# PULSE_COUNTER.net
KiCad netlist of a schematic drawn in Altium Designer
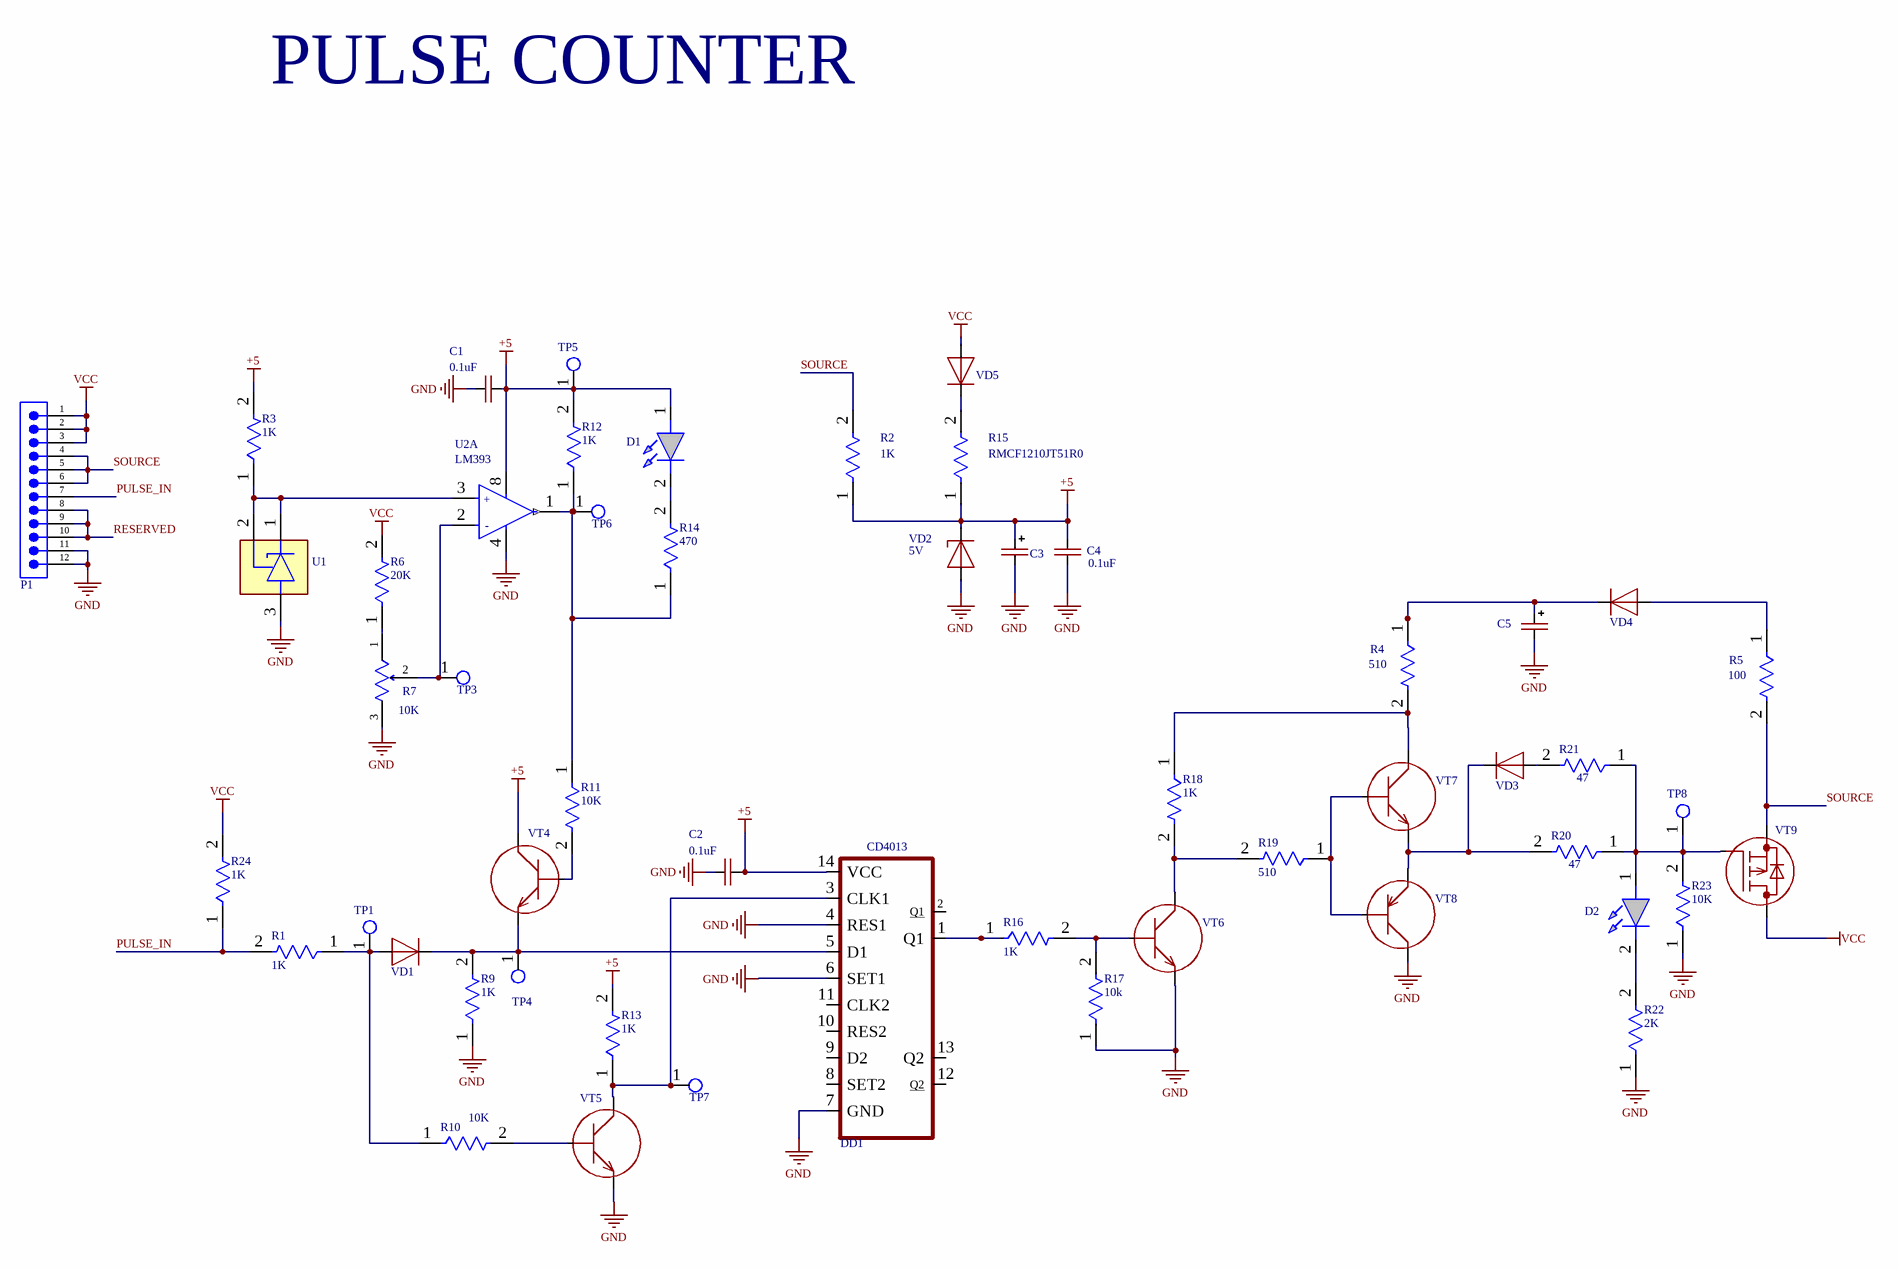
[diagram p0: PULSE COUNTER.SchDoc]

(export (version "E")
  (design (tool "Eeschema 10.0.6"))
  (components
    (comp (ref "C1")
      (value "0.1uF")
      (footprint "CAP-0805")
      (libsource (lib "PASSIVE_COMPONENTS") (part "CAP-NON-POLAR"))
    )
    (comp (ref "C2")
      (value "0.1uF")
      (footprint "CAP-0805")
      (libsource (lib "PASSIVE_COMPONENTS") (part "CAP-NON-POLAR"))
    )
    (comp (ref "C3")
      (value "CAP-POLAR")
      (footprint "CAP-TAN-D")
      (libsource (lib "PASSIVE_COMPONENTS") (part "CAP-POLAR"))
    )
    (comp (ref "C4")
      (value "0.1uF")
      (footprint "CAP-0805")
      (libsource (lib "PASSIVE_COMPONENTS") (part "CAP-NON-POLAR"))
    )
    (comp (ref "C5")
      (value "CAP-POLAR")
      (footprint "SIZE_EEE")
      (libsource (lib "PASSIVE_COMPONENTS") (part "CAP-POLAR"))
    )
    (comp (ref "D1")
      (value "151031YS06000")
      (footprint "LED_RED")
      (description "WURTH ELEKTRONIK - 151031YS06000 - LED, Yellow, Through Hole, T-1 (3mm), 30 mA, 2 V, 590 nm")
      (fields (field (name "MOUSER PART NUMBER") "710-151031YS06000"))
      (libsource (lib "Optic-LED") (part "LED"))
    )
    (comp (ref "D2")
      (value "151031YS06000")
      (footprint "LED_RED")
      (description "WURTH ELEKTRONIK - 151031YS06000 - LED, Yellow, Through Hole, T-1 (3mm), 30 mA, 2 V, 590 nm")
      (fields (field (name "MOUSER PART NUMBER") "710-151031YS06000"))
      (libsource (lib "Optic-LED") (part "LED"))
    )
    (comp (ref "DD1") (value "CD4013") (footprint "SO14-150") (libsource (lib "CD4013") (part "CD4013")))
    (comp (ref "P1")
      (value "61301211021")
      (footprint "61301211021")
      (description "WR-PHD Pin Header, THT, Angled, pitch 2.54mm, 1 Row, 12P")
      (fields (field (name "MANUFACTURER") "Wurth Elektronik"))
      (libsource (lib "Altium_WR-PHD (rev22b)") (part "61301211021"))
    )
    (comp (ref "R1")
      (value "1K")
      (footprint "RES-0805")
      (libsource (lib "PASSIVE_COMPONENTS") (part "RES-CONST"))
    )
    (comp (ref "R2")
      (value "1K")
      (footprint "FP-RMCF1210-MFG")
      (fields (field (name "TOLERANCE") "5%"))
      (libsource (lib "Altium Content Vault") (part "1029c3af85768c4190bb7ad29bc67b5"))
    )
    (comp (ref "R3")
      (value "1K")
      (footprint "RES-0805")
      (libsource (lib "PASSIVE_COMPONENTS") (part "RES-CONST"))
    )
    (comp (ref "R4")
      (value "510")
      (footprint "RES-0805")
      (libsource (lib "PASSIVE_COMPONENTS") (part "RES-CONST"))
    )
    (comp (ref "R5")
      (value "100")
      (footprint "RES-0805")
      (description "510")
      (libsource (lib "PASSIVE_COMPONENTS") (part "RES-CONST"))
    )
    (comp (ref "R6")
      (value "20K")
      (footprint "RES-0805")
      (libsource (lib "PASSIVE_COMPONENTS") (part "RES-CONST"))
    )
    (comp (ref "R7")
      (value "10K")
      (footprint "RES_Adj_3296W_Bourns")
      (libsource (lib "PASSIVE_COMPONENTS") (part "RES_Adj"))
    )
    (comp (ref "R9")
      (value "1K")
      (footprint "RES-0805")
      (libsource (lib "PASSIVE_COMPONENTS") (part "RES-CONST"))
    )
    (comp (ref "R10")
      (value "10K")
      (footprint "RES-0805")
      (libsource (lib "PASSIVE_COMPONENTS") (part "RES-CONST"))
    )
    (comp (ref "R11")
      (value "10K")
      (footprint "RES-0805")
      (libsource (lib "PASSIVE_COMPONENTS") (part "RES-CONST"))
    )
    (comp (ref "R12")
      (value "1K")
      (footprint "RES-0805")
      (libsource (lib "PASSIVE_COMPONENTS") (part "RES-CONST"))
    )
    (comp (ref "R13")
      (value "1K")
      (footprint "RES-0805")
      (libsource (lib "PASSIVE_COMPONENTS") (part "RES-CONST"))
    )
    (comp (ref "R14")
      (value "470")
      (footprint "RES-0805")
      (description "1K")
      (libsource (lib "PASSIVE_COMPONENTS") (part "RES-CONST"))
    )
    (comp (ref "R15")
      (value "RMCF1210JT51R0")
      (footprint "FP-RMCF1210-MFG")
      (description "51Ω ±5% 0.5W 1210 Thick Film Chip Resistor AEC-Q200 compliant")
      (fields (field (name "TOLERANCE") "5%"))
      (libsource (lib "Altium Content Vault") (part "1029c3af85768c4190bb7ad29bc67b5"))
    )
    (comp (ref "R16")
      (value "1K")
      (footprint "RES-0805")
      (description "10K")
      (libsource (lib "PASSIVE_COMPONENTS") (part "RES-CONST"))
    )
    (comp (ref "R17")
      (value "10k")
      (footprint "RES-0805")
      (description "10K")
      (libsource (lib "PASSIVE_COMPONENTS") (part "RES-CONST"))
    )
    (comp (ref "R18")
      (value "1K")
      (footprint "RES-0805")
      (description "10K")
      (libsource (lib "PASSIVE_COMPONENTS") (part "RES-CONST"))
    )
    (comp (ref "R19")
      (value "510")
      (footprint "RES-0805")
      (libsource (lib "PASSIVE_COMPONENTS") (part "RES-CONST"))
    )
    (comp (ref "R20")
      (value "47")
      (footprint "RES-0805")
      (description "10K")
      (libsource (lib "PASSIVE_COMPONENTS") (part "RES-CONST"))
    )
    (comp (ref "R21")
      (value "47")
      (footprint "RES-0805")
      (description "10K")
      (libsource (lib "PASSIVE_COMPONENTS") (part "RES-CONST"))
    )
    (comp (ref "R22")
      (value "2K")
      (footprint "RES-0805")
      (libsource (lib "PASSIVE_COMPONENTS") (part "RES-CONST"))
    )
    (comp (ref "R23")
      (value "10K")
      (footprint "RES-0805")
      (libsource (lib "PASSIVE_COMPONENTS") (part "RES-CONST"))
    )
    (comp (ref "R24")
      (value "1K")
      (footprint "RES-0805")
      (libsource (lib "PASSIVE_COMPONENTS") (part "RES-CONST"))
    )
    (comp (ref "TP1")
      (value "~")
      (footprint "Test_Point")
      (description "Test_Point")
      (libsource (lib "Connectors") (part "TP_PCB?"))
    )
    (comp (ref "TP3")
      (value "~")
      (footprint "Test_Point")
      (description "Test_Point")
      (libsource (lib "Connectors") (part "TP_PCB?"))
    )
    (comp (ref "TP4")
      (value "~")
      (footprint "Test_Point")
      (description "Test_Point")
      (libsource (lib "Connectors") (part "TP_PCB?"))
    )
    (comp (ref "TP5")
      (value "~")
      (footprint "Test_Point")
      (description "Test_Point")
      (libsource (lib "Connectors") (part "TP_PCB?"))
    )
    (comp (ref "TP6")
      (value "~")
      (footprint "Test_Point")
      (description "Test_Point")
      (libsource (lib "Connectors") (part "TP_PCB?"))
    )
    (comp (ref "TP7")
      (value "~")
      (footprint "Test_Point")
      (description "Test_Point")
      (libsource (lib "Connectors") (part "TP_PCB?"))
    )
    (comp (ref "TP8")
      (value "~")
      (footprint "Test_Point")
      (description "Test_Point")
      (libsource (lib "Connectors") (part "TP_PCB?"))
    )
    (comp (ref "U1")
      (value "TL431")
      (footprint "TL431_SOT-23-3(A)")
      (description "TL431_SOT-23-3")
      (libsource (lib "Diodes") (part "TL431_SOT-23-3"))
    )
    (comp (ref "U2")
      (value "LM393")
      (footprint "FP-751-07-IPC_C")
      (description "IC OPAMP GP 2 CIRCUIT 8SOIC")
      (libsource (lib "Altium Content Vault") (part "992a6607d1d88c80ee6b45e5ba6cb1b"))
    )
    (comp (ref "VD1") (value "DIODE") (footprint "DO-214AC, SMA") (libsource (lib "DO214") (part "DIODE")))
    (comp (ref "VD2") (value "5V") (footprint "DO-017AA") (libsource (lib "Diodes") (part "ZENER")))
    (comp (ref "VD3") (value "DIODE") (footprint "DO-214AC, SMA") (libsource (lib "DO214") (part "DIODE")))
    (comp (ref "VD4") (value "DIODE") (footprint "DO-214AC, SMA") (libsource (lib "DO214") (part "DIODE")))
    (comp (ref "VD5") (value "DIODE") (footprint "DO-214AC, SMA") (libsource (lib "DO214") (part "DIODE")))
    (comp (ref "VT4") (value "BC847-BEC") (footprint "SOT23-3") (libsource (lib "BC8XX") (part "BC847-BEC")))
    (comp (ref "VT5") (value "BC847-BEC") (footprint "SOT23-3") (libsource (lib "BC8XX") (part "BC847-BEC")))
    (comp (ref "VT6") (value "BC847-BEC") (footprint "SOT23-3") (libsource (lib "BC8XX") (part "BC847-BEC")))
    (comp (ref "VT7") (value "BC847-BEC") (footprint "SOT23-3") (libsource (lib "BC8XX") (part "BC847-BEC")))
    (comp (ref "VT8") (value "BC857-BEC") (footprint "SOT23-3") (libsource (lib "BC8XX") (part "BC857-BEC")))
    (comp (ref "VT9")
      (value "MOSFET-P-CH-DPAK")
      (footprint "DPAK")
      (libsource (lib "IRFR9120N") (part "MOSFET-P-CH-DPAK"))
    )
  )
  (nets
    (net (code "1") (name "+5") (class "Default")
      (node (ref "C1") (pin "2") (pinfunction "2_2") (pintype "passive"))
      (node (ref "C2") (pin "2") (pinfunction "2_2") (pintype "passive"))
      (node (ref "C3") (pin "1") (pinfunction "+_1") (pintype "passive"))
      (node (ref "C4") (pin "2") (pinfunction "2_2") (pintype "passive"))
      (node (ref "D1") (pin "1") (pinfunction "A_1") (pintype "passive"))
      (node (ref "DD1") (pin "14") (pinfunction "VCC_14") (pintype "passive"))
      (node (ref "R12") (pin "2") (pinfunction "2_2") (pintype "passive"))
      (node (ref "R13") (pin "2") (pinfunction "2_2") (pintype "passive"))
      (node (ref "R15") (pin "1") (pinfunction "1_1") (pintype "passive"))
      (node (ref "R2") (pin "1") (pinfunction "1_1") (pintype "passive"))
      (node (ref "R3") (pin "2") (pinfunction "2_2") (pintype "passive"))
      (node (ref "TP5") (pin "1") (pinfunction "G9_1") (pintype "passive"))
      (node (ref "U2") (pin "8") (pinfunction "VCC_8") (pintype "power_in"))
      (node (ref "VD2") (pin "1") (pinfunction "C_1") (pintype "passive"))
      (node (ref "VT4") (pin "3") (pinfunction "C_3") (pintype "passive"))
    )
    (net (code "2") (name "/PULSE_IN") (class "Default")
      (node (ref "P1") (pin "7") (pinfunction "7_7") (pintype "passive"))
      (node (ref "R1") (pin "2") (pinfunction "2_2") (pintype "passive"))
      (node (ref "R24") (pin "1") (pinfunction "1_1") (pintype "passive"))
    )
    (net (code "3") (name "/RESERVED") (class "Default")
      (node (ref "P1") (pin "10") (pinfunction "10_10") (pintype "passive"))
      (node (ref "P1") (pin "8") (pinfunction "8_8") (pintype "passive"))
      (node (ref "P1") (pin "9") (pinfunction "9_9") (pintype "passive"))
    )
    (net (code "4") (name "/SOURCE") (class "Default")
      (node (ref "P1") (pin "4") (pinfunction "4_4") (pintype "passive"))
      (node (ref "P1") (pin "5") (pinfunction "5_5") (pintype "passive"))
      (node (ref "P1") (pin "6") (pinfunction "6_6") (pintype "passive"))
      (node (ref "R2") (pin "2") (pinfunction "2_2") (pintype "passive"))
      (node (ref "R5") (pin "2") (pinfunction "2_2") (pintype "passive"))
      (node (ref "VT9") (pin "3") (pinfunction "S_3") (pintype "passive"))
    )
    (net (code "5") (name "GND") (class "Default")
      (node (ref "C1") (pin "1") (pinfunction "1_1") (pintype "passive"))
      (node (ref "C2") (pin "1") (pinfunction "1_1") (pintype "passive"))
      (node (ref "C3") (pin "2") (pinfunction "-_2") (pintype "passive"))
      (node (ref "C4") (pin "1") (pinfunction "1_1") (pintype "passive"))
      (node (ref "C5") (pin "2") (pinfunction "-_2") (pintype "passive"))
      (node (ref "DD1") (pin "4") (pinfunction "RES1_4") (pintype "passive"))
      (node (ref "DD1") (pin "6") (pinfunction "SET1_6") (pintype "passive"))
      (node (ref "DD1") (pin "7") (pinfunction "GND_7") (pintype "passive"))
      (node (ref "P1") (pin "11") (pinfunction "11_11") (pintype "passive"))
      (node (ref "P1") (pin "12") (pinfunction "12_12") (pintype "passive"))
      (node (ref "R17") (pin "1") (pinfunction "1_1") (pintype "passive"))
      (node (ref "R22") (pin "1") (pinfunction "1_1") (pintype "passive"))
      (node (ref "R23") (pin "1") (pinfunction "1_1") (pintype "passive"))
      (node (ref "R7") (pin "3") (pinfunction "CW_3") (pintype "passive"))
      (node (ref "R9") (pin "1") (pinfunction "1_1") (pintype "passive"))
      (node (ref "U1") (pin "3") (pinfunction "A_3") (pintype "passive"))
      (node (ref "U2") (pin "4") (pinfunction "VEE/GND_4") (pintype "power_in"))
      (node (ref "VD2") (pin "2") (pinfunction "A_2") (pintype "passive"))
      (node (ref "VT5") (pin "2") (pinfunction "E_2") (pintype "passive"))
      (node (ref "VT6") (pin "2") (pinfunction "E_2") (pintype "passive"))
      (node (ref "VT8") (pin "3") (pinfunction "C_3") (pintype "passive"))
    )
    (net (code "6") (name "Net-(C5-+)") (class "Default")
      (node (ref "C5") (pin "1") (pinfunction "+_1") (pintype "passive"))
      (node (ref "R4") (pin "1") (pinfunction "1_1") (pintype "passive"))
      (node (ref "VD4") (pin "1") (pinfunction "C_1") (pintype "passive"))
    )
    (net (code "7") (name "Net-(D1-K)") (class "Default")
      (node (ref "D1") (pin "2") (pinfunction "K_2") (pintype "passive"))
      (node (ref "R14") (pin "2") (pinfunction "2_2") (pintype "passive"))
    )
    (net (code "8") (name "Net-(D2-A)") (class "Default")
      (node (ref "D2") (pin "1") (pinfunction "A_1") (pintype "passive"))
      (node (ref "R20") (pin "1") (pinfunction "1_1") (pintype "passive"))
      (node (ref "R21") (pin "1") (pinfunction "1_1") (pintype "passive"))
      (node (ref "R23") (pin "2") (pinfunction "2_2") (pintype "passive"))
      (node (ref "TP8") (pin "1") (pinfunction "G9_1") (pintype "passive"))
      (node (ref "VT9") (pin "1") (pinfunction "G_1") (pintype "passive"))
    )
    (net (code "9") (name "Net-(D2-K)") (class "Default")
      (node (ref "D2") (pin "2") (pinfunction "K_2") (pintype "passive"))
      (node (ref "R22") (pin "2") (pinfunction "2_2") (pintype "passive"))
    )
    (net (code "10") (name "Net-(DD1-CLK1)") (class "Default")
      (node (ref "DD1") (pin "3") (pinfunction "CLK1_3") (pintype "passive"))
      (node (ref "R13") (pin "1") (pinfunction "1_1") (pintype "passive"))
      (node (ref "TP7") (pin "1") (pinfunction "G9_1") (pintype "passive"))
      (node (ref "VT5") (pin "3") (pinfunction "C_3") (pintype "passive"))
    )
    (net (code "11") (name "Net-(DD1-D1)") (class "Default")
      (node (ref "DD1") (pin "5") (pinfunction "D1_5") (pintype "passive"))
      (node (ref "R9") (pin "2") (pinfunction "2_2") (pintype "passive"))
      (node (ref "TP4") (pin "1") (pinfunction "G9_1") (pintype "passive"))
      (node (ref "VD1") (pin "1") (pinfunction "C_1") (pintype "passive"))
      (node (ref "VT4") (pin "2") (pinfunction "E_2") (pintype "passive"))
    )
    (net (code "12") (name "Net-(DD1-Q1-Pad1)") (class "Default")
      (node (ref "DD1") (pin "1") (pinfunction "Q1_1") (pintype "passive"))
      (node (ref "R16") (pin "1") (pinfunction "1_1") (pintype "passive"))
    )
    (net (code "13") (name "Net-(R7-CCW)") (class "Default")
      (node (ref "R6") (pin "1") (pinfunction "1_1") (pintype "passive"))
      (node (ref "R7") (pin "1") (pinfunction "CCW_1") (pintype "passive"))
    )
    (net (code "14") (name "Net-(R7-WIPER)") (class "Default")
      (node (ref "R7") (pin "2") (pinfunction "WIPER_2") (pintype "passive"))
      (node (ref "TP3") (pin "1") (pinfunction "G9_1") (pintype "passive"))
      (node (ref "U2") (pin "2") (pinfunction "INPUT_A-_2") (pintype "tri_state"))
    )
    (net (code "15") (name "Net-(TP1-G9)") (class "Default")
      (node (ref "R1") (pin "1") (pinfunction "1_1") (pintype "passive"))
      (node (ref "R10") (pin "1") (pinfunction "1_1") (pintype "passive"))
      (node (ref "TP1") (pin "1") (pinfunction "G9_1") (pintype "passive"))
      (node (ref "VD1") (pin "2") (pinfunction "A_2") (pintype "passive"))
    )
    (net (code "16") (name "Net-(TP6-G9)") (class "Default")
      (node (ref "R11") (pin "1") (pinfunction "1_1") (pintype "passive"))
      (node (ref "R12") (pin "1") (pinfunction "1_1") (pintype "passive"))
      (node (ref "R14") (pin "1") (pinfunction "1_1") (pintype "passive"))
      (node (ref "TP6") (pin "1") (pinfunction "G9_1") (pintype "passive"))
      (node (ref "U2") (pin "1") (pinfunction "OUTPUT_A_1") (pintype "output"))
    )
    (net (code "17") (name "Net-(U1-C)") (class "Default")
      (node (ref "R3") (pin "1") (pinfunction "1_1") (pintype "passive"))
      (node (ref "U1") (pin "1") (pinfunction "C_1") (pintype "passive"))
      (node (ref "U1") (pin "2") (pinfunction "REF_2") (pintype "passive"))
      (node (ref "U2") (pin "3") (pinfunction "INPUT_A+_3") (pintype "tri_state"))
    )
    (net (code "18") (name "Net-(VD3-A)") (class "Default")
      (node (ref "R21") (pin "2") (pinfunction "2_2") (pintype "passive"))
      (node (ref "VD3") (pin "2") (pinfunction "A_2") (pintype "passive"))
    )
    (net (code "19") (name "Net-(VD3-C)") (class "Default")
      (node (ref "R20") (pin "2") (pinfunction "2_2") (pintype "passive"))
      (node (ref "VD3") (pin "1") (pinfunction "C_1") (pintype "passive"))
      (node (ref "VT7") (pin "2") (pinfunction "E_2") (pintype "passive"))
      (node (ref "VT8") (pin "2") (pinfunction "E_2") (pintype "passive"))
    )
    (net (code "20") (name "Net-(VD4-A)") (class "Default")
      (node (ref "R5") (pin "1") (pinfunction "1_1") (pintype "passive"))
      (node (ref "VD4") (pin "2") (pinfunction "A_2") (pintype "passive"))
    )
    (net (code "21") (name "Net-(VD5-C)") (class "Default")
      (node (ref "R15") (pin "2") (pinfunction "2_2") (pintype "passive"))
      (node (ref "VD5") (pin "1") (pinfunction "C_1") (pintype "passive"))
    )
    (net (code "22") (name "Net-(VT4-B)") (class "Default")
      (node (ref "R11") (pin "2") (pinfunction "2_2") (pintype "passive"))
      (node (ref "VT4") (pin "1") (pinfunction "B_1") (pintype "passive"))
    )
    (net (code "23") (name "Net-(VT5-B)") (class "Default")
      (node (ref "R10") (pin "2") (pinfunction "2_2") (pintype "passive"))
      (node (ref "VT5") (pin "1") (pinfunction "B_1") (pintype "passive"))
    )
    (net (code "24") (name "Net-(VT6-B)") (class "Default")
      (node (ref "R16") (pin "2") (pinfunction "2_2") (pintype "passive"))
      (node (ref "R17") (pin "2") (pinfunction "2_2") (pintype "passive"))
      (node (ref "VT6") (pin "1") (pinfunction "B_1") (pintype "passive"))
    )
    (net (code "25") (name "Net-(VT6-C)") (class "Default")
      (node (ref "R18") (pin "2") (pinfunction "2_2") (pintype "passive"))
      (node (ref "R19") (pin "2") (pinfunction "2_2") (pintype "passive"))
      (node (ref "VT6") (pin "3") (pinfunction "C_3") (pintype "passive"))
    )
    (net (code "26") (name "Net-(VT7-B)") (class "Default")
      (node (ref "R19") (pin "1") (pinfunction "1_1") (pintype "passive"))
      (node (ref "VT7") (pin "1") (pinfunction "B_1") (pintype "passive"))
      (node (ref "VT8") (pin "1") (pinfunction "B_1") (pintype "passive"))
    )
    (net (code "27") (name "Net-(VT7-C)") (class "Default")
      (node (ref "R18") (pin "1") (pinfunction "1_1") (pintype "passive"))
      (node (ref "R4") (pin "2") (pinfunction "2_2") (pintype "passive"))
      (node (ref "VT7") (pin "3") (pinfunction "C_3") (pintype "passive"))
    )
    (net (code "28") (name "VCC") (class "Default")
      (node (ref "P1") (pin "1") (pinfunction "1_1") (pintype "passive"))
      (node (ref "P1") (pin "2") (pinfunction "2_2") (pintype "passive"))
      (node (ref "P1") (pin "3") (pinfunction "3_3") (pintype "passive"))
      (node (ref "R24") (pin "2") (pinfunction "2_2") (pintype "passive"))
      (node (ref "R6") (pin "2") (pinfunction "2_2") (pintype "passive"))
      (node (ref "VD5") (pin "2") (pinfunction "A_2") (pintype "passive"))
      (node (ref "VT9") (pin "4") (pinfunction "D_4") (pintype "passive"))
    )
    (net (code "29") (name "unconnected-(DD1-CLK2-Pad11)") (class "Default")
      (node (ref "DD1") (pin "11") (pinfunction "CLK2_11") (pintype "passive"))
    )
    (net (code "30") (name "unconnected-(DD1-D2-Pad9)") (class "Default")
      (node (ref "DD1") (pin "9") (pinfunction "D2_9") (pintype "passive"))
    )
    (net (code "31") (name "unconnected-(DD1-Q1-Pad2)") (class "Default")
      (node (ref "DD1") (pin "2") (pinfunction "Q1_2") (pintype "passive"))
    )
    (net (code "32") (name "unconnected-(DD1-Q2-Pad12)") (class "Default")
      (node (ref "DD1") (pin "12") (pinfunction "Q2_12") (pintype "passive"))
    )
    (net (code "33") (name "unconnected-(DD1-Q2-Pad13)") (class "Default")
      (node (ref "DD1") (pin "13") (pinfunction "Q2_13") (pintype "passive"))
    )
    (net (code "34") (name "unconnected-(DD1-RES2-Pad10)") (class "Default")
      (node (ref "DD1") (pin "10") (pinfunction "RES2_10") (pintype "passive"))
    )
    (net (code "35") (name "unconnected-(DD1-SET2-Pad8)") (class "Default")
      (node (ref "DD1") (pin "8") (pinfunction "SET2_8") (pintype "passive"))
    )
  )
)
